# Top.net
KiCad netlist of a schematic drawn in Altium Designer
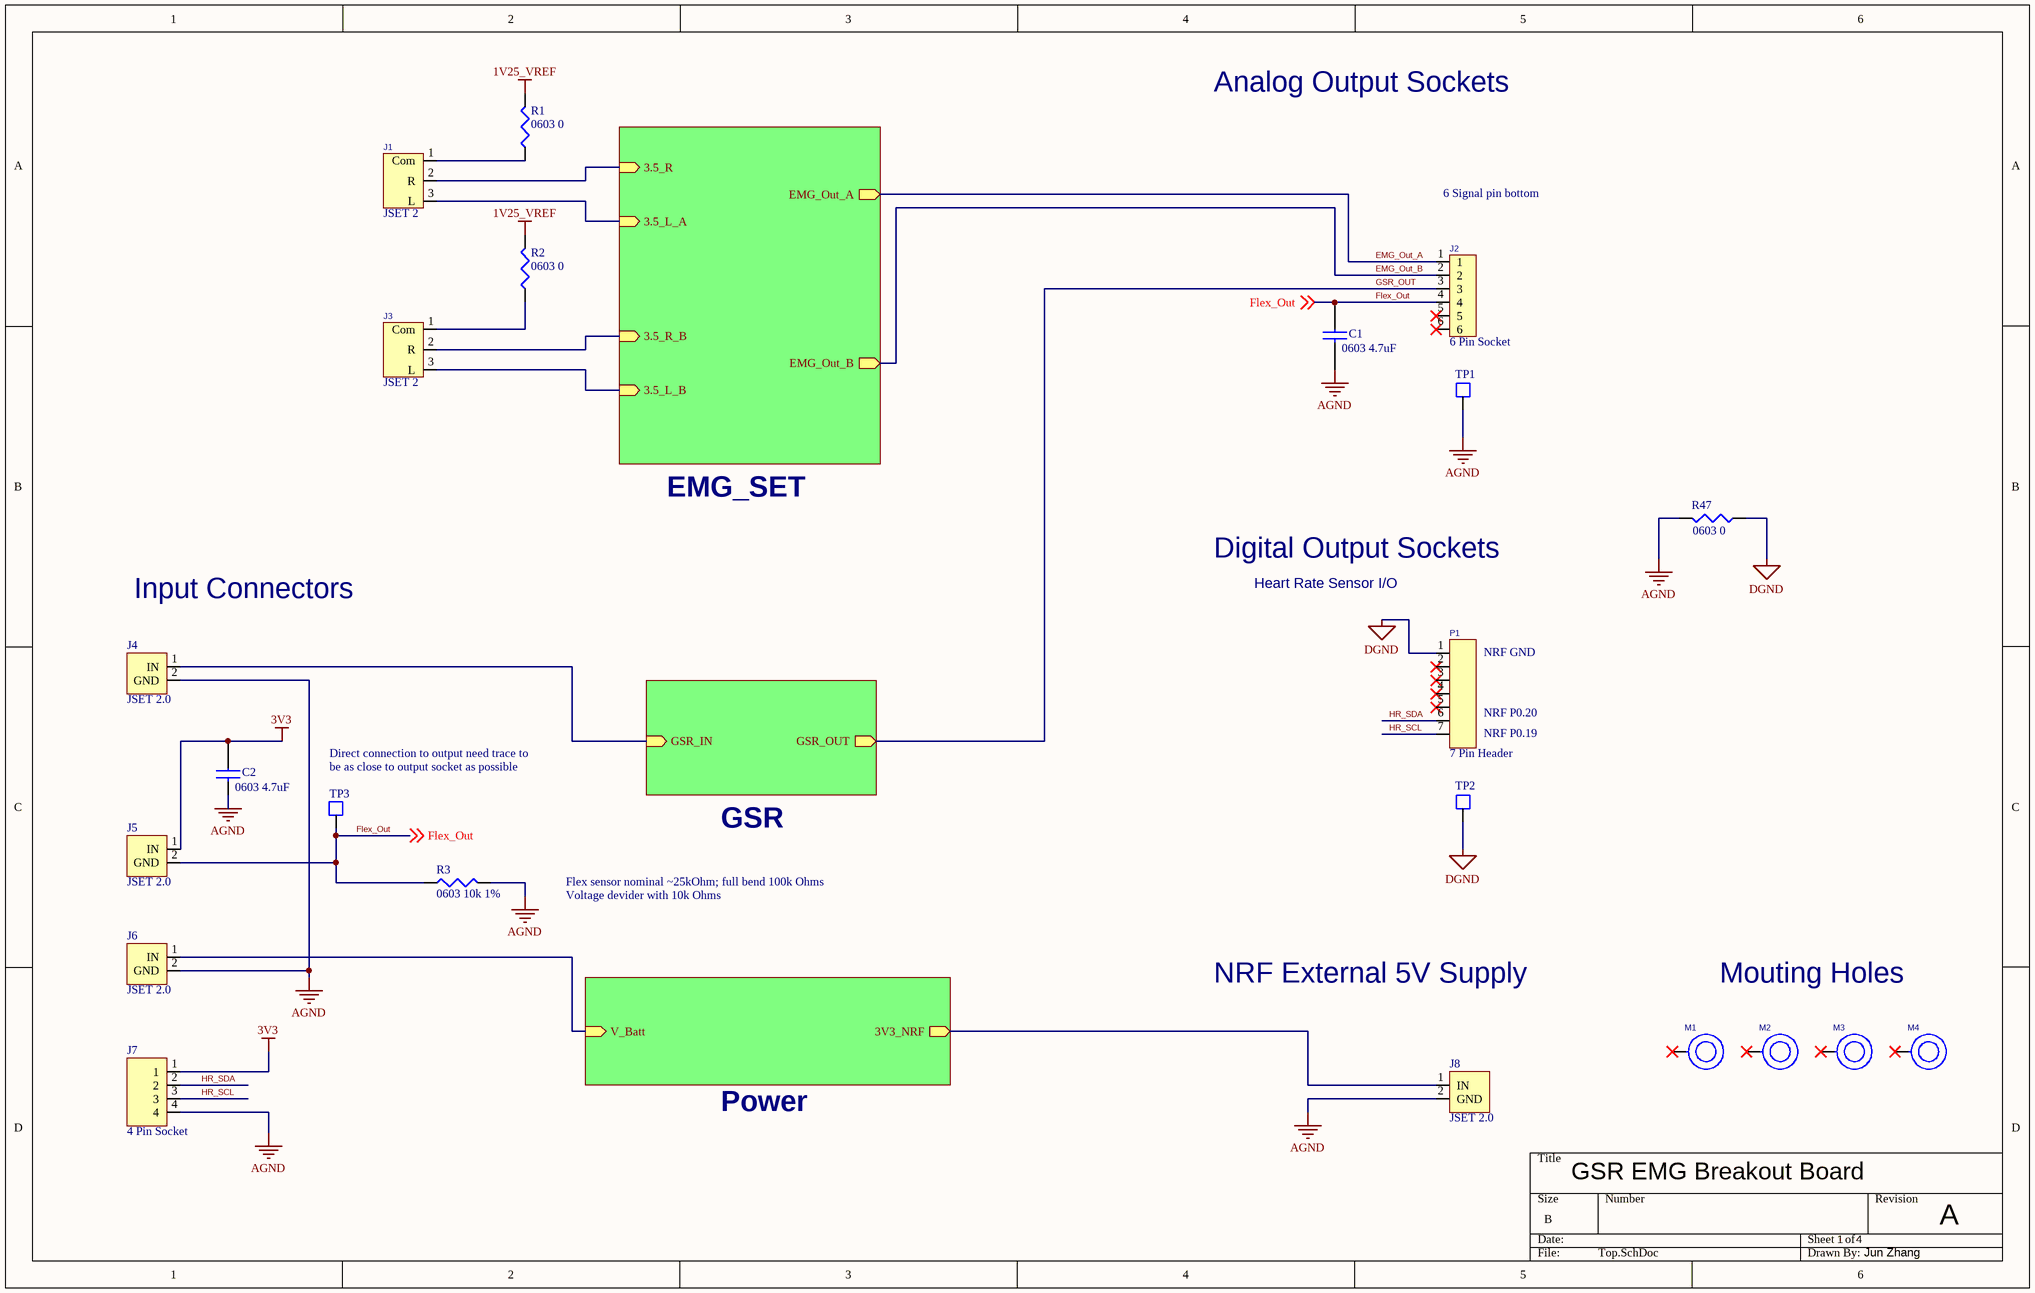
[diagram p0: Top.SchDoc]

(export (version "E")
  (design (tool "Eeschema 10.0.6"))
  (components
    (comp (ref "C1")
      (value "0603 4.7uF")
      (footprint "CAP_0603_CER")
      (description "Generic Cap for NC (No Polar)\r\nESR <30mOhm\r\nESL <1.5nH,\r\nX5R")
      (fields
        (field (name "MANUFACTURER") "Samsung Electro-Mechanics")
        (field (name "MANUFACTURER PART NUMBER") "CL10A475KO8NNNC")
      )
      (libsource (lib "BioSens") (part "CAP_NP"))
    )
    (comp (ref "C2")
      (value "0603 4.7uF")
      (footprint "CAP_0603_CER")
      (description "Generic Cap for NC (No Polar)\r\nESR <30mOhm\r\nESL <1.5nH,\r\nX5R")
      (fields
        (field (name "MANUFACTURER") "Samsung Electro-Mechanics")
        (field (name "MANUFACTURER PART NUMBER") "CL10A475KO8NNNC")
      )
      (libsource (lib "BioSens") (part "CAP_NP"))
    )
    (comp (ref "J1")
      (value "JSET 2")
      (footprint "JST-XH3A")
      (description "JST-XH3A")
      (libsource (lib "BioSens") (part "JST 3 Pin"))
    )
    (comp (ref "J2")
      (value "6 Pin Socket")
      (footprint "6 Pin Header")
      (description "Headers for Signal to NRF")
      (libsource (lib "BioSens") (part "6 Pin Socket"))
    )
    (comp (ref "J3")
      (value "JSET 2")
      (footprint "JST-XH3A")
      (description "JST-XH3A")
      (libsource (lib "BioSens") (part "JST 3 Pin"))
    )
    (comp (ref "J4")
      (value "JSET 2.0")
      (footprint "JST_XH2A")
      (description "PA Series 2 Position 2 mm Pitch Top Entry No Boss Through Hole Shrouded Header")
      (fields
        (field (name "MANUFACTURER") "JST")
        (field (name "MANUFACTURER PART NUMBER") "B02B-PASK(LF)(SN)")
      )
      (libsource (lib "") (part "JST 2 Pin_1"))
    )
    (comp (ref "J5")
      (value "JSET 2.0")
      (footprint "JST_XH2A")
      (description "PA Series 2 Position 2 mm Pitch Top Entry No Boss Through Hole Shrouded Header")
      (fields
        (field (name "MANUFACTURER") "JST")
        (field (name "MANUFACTURER PART NUMBER") "B02B-PASK(LF)(SN)")
      )
      (libsource (lib "") (part "JST 2 Pin_1"))
    )
    (comp (ref "J6")
      (value "JSET 2.0")
      (footprint "JST_XH2A")
      (description "PA Series 2 Position 2 mm Pitch Top Entry No Boss Through Hole Shrouded Header")
      (fields
        (field (name "MANUFACTURER") "JST")
        (field (name "MANUFACTURER PART NUMBER") "B02B-PASK(LF)(SN)")
      )
      (libsource (lib "") (part "JST 2 Pin_1"))
    )
    (comp (ref "J7")
      (value "4 Pin Socket")
      (footprint "JST-XH4A")
      (description "Connector Header, PA Series, Top Entry , 4 Position, Male Pin, 1 Row, 2.0mm, Through Hole, Natural")
      (fields
        (field (name "MANUFACTURER") "JST")
        (field (name "MANUFACTURER PART NUMBER") "B04B-PASK(LF)(SN)")
      )
      (libsource (lib "BioSens") (part "JST 4 Pin"))
    )
    (comp (ref "J8")
      (value "JSET 2.0")
      (footprint "JST_XH2A")
      (description "PA Series 2 Position 2 mm Pitch Top Entry No Boss Through Hole Shrouded Header")
      (fields
        (field (name "MANUFACTURER") "JST")
        (field (name "MANUFACTURER PART NUMBER") "B02B-PASK(LF)(SN)")
      )
      (libsource (lib "BioSens") (part "JST 2 Pin"))
    )
    (comp (ref "M1")
      (value "Mounting Hole")
      (footprint "Mounting Hole")
      (libsource (lib "BioSens") (part "Mounting Hole"))
    )
    (comp (ref "M2")
      (value "Mounting Hole")
      (footprint "Mounting Hole")
      (libsource (lib "BioSens") (part "Mounting Hole"))
    )
    (comp (ref "M3")
      (value "Mounting Hole")
      (footprint "Mounting Hole")
      (libsource (lib "BioSens") (part "Mounting Hole"))
    )
    (comp (ref "M4")
      (value "Mounting Hole")
      (footprint "Mounting Hole")
      (libsource (lib "BioSens") (part "Mounting Hole"))
    )
    (comp (ref "P1")
      (value "7 Pin Header")
      (footprint "7 Pin Header")
      (description "KK 254 Wire-to-Board Header Single Row Vertical 7 Circuits PA Polyamide Nylon Tin (Sn) Plating")
      (fields (field (name "MANUFACTURER") "Molex") (field (name "MANUFACTURER PART NUMBER") "22-03-2071"))
      (libsource (lib "BioSens") (part "7 Pin Socket"))
    )
    (comp (ref "R1")
      (value "0603 0")
      (footprint "0603")
      (description "Generic Resistor")
      (fields (field (name "MANUFACTURER") "YAGEO"))
      (libsource (lib "BioSens") (part "RESISTOR"))
    )
    (comp (ref "R2")
      (value "0603 0")
      (footprint "0603")
      (description "Generic Resistor")
      (fields (field (name "MANUFACTURER") "YAGEO"))
      (libsource (lib "BioSens") (part "RESISTOR"))
    )
    (comp (ref "R3")
      (value "0603 10k 1%")
      (footprint "0603")
      (description "Generic Resistor")
      (fields (field (name "MANUFACTURER") "YAGEO"))
      (libsource (lib "BioSens") (part "RESISTOR"))
    )
    (comp (ref "R47")
      (value "0603 0")
      (footprint "0603")
      (description "Generic Resistor")
      (fields (field (name "MANUFACTURER") "YAGEO"))
      (libsource (lib "BioSens") (part "RESISTOR"))
    )
    (comp (ref "TP1")
      (value "0402_TEST_PT")
      (footprint "0402_PAD")
      (libsource (lib "BioSens") (part "0402_TEST_PT"))
    )
    (comp (ref "TP2")
      (value "0402_TEST_PT")
      (footprint "0402_PAD")
      (libsource (lib "BioSens") (part "0402_TEST_PT"))
    )
    (comp (ref "TP3")
      (value "0402_TEST_PT")
      (footprint "0402_PAD")
      (libsource (lib "BioSens") (part "0402_TEST_PT"))
    )
  )
  (nets
    (net (code "1") (name "/3.5_L_A") (class "Default")
      (node (ref "J1") (pin "3") (pinfunction "L_3") (pintype "passive"))
    )
    (net (code "2") (name "/3.5_L_B") (class "Default")
      (node (ref "J3") (pin "3") (pinfunction "L_3") (pintype "passive"))
    )
    (net (code "3") (name "/3.5_R") (class "Default")
      (node (ref "J1") (pin "2") (pinfunction "R_2") (pintype "passive"))
    )
    (net (code "4") (name "/3.5_R_B") (class "Default")
      (node (ref "J3") (pin "2") (pinfunction "R_2") (pintype "passive"))
    )
    (net (code "5") (name "/3V3_NRF") (class "Default")
      (node (ref "J8") (pin "1") (pinfunction "IN_1") (pintype "passive"))
    )
    (net (code "6") (name "/EMG_Out_A") (class "Default")
      (node (ref "J2") (pin "1") (pinfunction "1_1") (pintype "passive"))
    )
    (net (code "7") (name "/EMG_Out_B") (class "Default")
      (node (ref "J2") (pin "2") (pinfunction "2_2") (pintype "passive"))
    )
    (net (code "8") (name "/GSR_IN") (class "Default")
      (node (ref "J4") (pin "1") (pinfunction "IN_1") (pintype "passive"))
    )
    (net (code "9") (name "/GSR_OUT") (class "Default")
      (node (ref "J2") (pin "3") (pinfunction "3_3") (pintype "passive"))
    )
    (net (code "10") (name "/HR_SCL") (class "Default")
      (node (ref "J7") (pin "3") (pinfunction "3_3") (pintype "passive"))
      (node (ref "P1") (pin "7") (pintype "passive"))
    )
    (net (code "11") (name "/HR_SDA") (class "Default")
      (node (ref "J7") (pin "2") (pinfunction "2_2") (pintype "passive"))
      (node (ref "P1") (pin "6") (pintype "passive"))
    )
    (net (code "12") (name "/V_Batt") (class "Default")
      (node (ref "J6") (pin "1") (pinfunction "IN_1") (pintype "passive"))
    )
    (net (code "13") (name "1V25_VREF") (class "Default")
      (node (ref "R1") (pin "1") (pinfunction "1_1") (pintype "passive"))
      (node (ref "R2") (pin "1") (pinfunction "1_1") (pintype "passive"))
    )
    (net (code "14") (name "3V3") (class "Default")
      (node (ref "C2") (pin "1") (pinfunction "1_1") (pintype "passive"))
      (node (ref "J5") (pin "1") (pinfunction "IN_1") (pintype "passive"))
      (node (ref "J7") (pin "1") (pinfunction "1_1") (pintype "passive"))
    )
    (net (code "15") (name "AGND") (class "Default")
      (node (ref "C1") (pin "2") (pinfunction "2_2") (pintype "passive"))
      (node (ref "C2") (pin "2") (pinfunction "2_2") (pintype "passive"))
      (node (ref "J4") (pin "2") (pinfunction "GND_2") (pintype "passive"))
      (node (ref "J6") (pin "2") (pinfunction "GND_2") (pintype "passive"))
      (node (ref "J7") (pin "4") (pinfunction "4_4") (pintype "passive"))
      (node (ref "J8") (pin "2") (pinfunction "GND_2") (pintype "passive"))
      (node (ref "R3") (pin "2") (pinfunction "2_2") (pintype "passive"))
      (node (ref "R47") (pin "1") (pinfunction "1_1") (pintype "passive"))
      (node (ref "TP1") (pin "1") (pintype "passive"))
    )
    (net (code "16") (name "DGND") (class "Default")
      (node (ref "P1") (pin "1") (pintype "passive"))
      (node (ref "R47") (pin "2") (pinfunction "2_2") (pintype "passive"))
      (node (ref "TP2") (pin "1") (pintype "passive"))
    )
    (net (code "17") (name "Flex_Out") (class "Default")
      (node (ref "C1") (pin "1") (pinfunction "1_1") (pintype "passive"))
      (node (ref "J2") (pin "4") (pinfunction "4_4") (pintype "passive"))
      (node (ref "J5") (pin "2") (pinfunction "GND_2") (pintype "passive"))
      (node (ref "R3") (pin "1") (pinfunction "1_1") (pintype "passive"))
      (node (ref "TP3") (pin "1") (pintype "passive"))
    )
    (net (code "18") (name "Net-(J1-Com)") (class "Default")
      (node (ref "J1") (pin "1") (pinfunction "Com_1") (pintype "passive"))
      (node (ref "R1") (pin "2") (pinfunction "2_2") (pintype "passive"))
    )
    (net (code "19") (name "Net-(J3-Com)") (class "Default")
      (node (ref "J3") (pin "1") (pinfunction "Com_1") (pintype "passive"))
      (node (ref "R2") (pin "2") (pinfunction "2_2") (pintype "passive"))
    )
    (net (code "20") (name "unconnected-(J2-Pad5)") (class "Default")
      (node (ref "J2") (pin "5") (pinfunction "5_5") (pintype "passive+no_connect"))
    )
    (net (code "21") (name "unconnected-(J2-Pad6)") (class "Default")
      (node (ref "J2") (pin "6") (pinfunction "6_6") (pintype "passive+no_connect"))
    )
    (net (code "22") (name "unconnected-(M1-Pad1)") (class "Default")
      (node (ref "M1") (pin "1") (pinfunction "1_1") (pintype "passive+no_connect"))
    )
    (net (code "23") (name "unconnected-(M2-Pad1)") (class "Default")
      (node (ref "M2") (pin "1") (pinfunction "1_1") (pintype "passive+no_connect"))
    )
    (net (code "24") (name "unconnected-(M3-Pad1)") (class "Default")
      (node (ref "M3") (pin "1") (pinfunction "1_1") (pintype "passive+no_connect"))
    )
    (net (code "25") (name "unconnected-(M4-Pad1)") (class "Default")
      (node (ref "M4") (pin "1") (pinfunction "1_1") (pintype "passive+no_connect"))
    )
    (net (code "26") (name "unconnected-(P1-Pad2)") (class "Default")
      (node (ref "P1") (pin "2") (pintype "passive+no_connect"))
    )
    (net (code "27") (name "unconnected-(P1-Pad3)") (class "Default")
      (node (ref "P1") (pin "3") (pintype "passive+no_connect"))
    )
    (net (code "28") (name "unconnected-(P1-Pad4)") (class "Default")
      (node (ref "P1") (pin "4") (pintype "passive+no_connect"))
    )
    (net (code "29") (name "unconnected-(P1-Pad5)") (class "Default")
      (node (ref "P1") (pin "5") (pintype "passive+no_connect"))
    )
  )
)
